# Commander.net
KiCad netlist of a schematic drawn in EAGLE
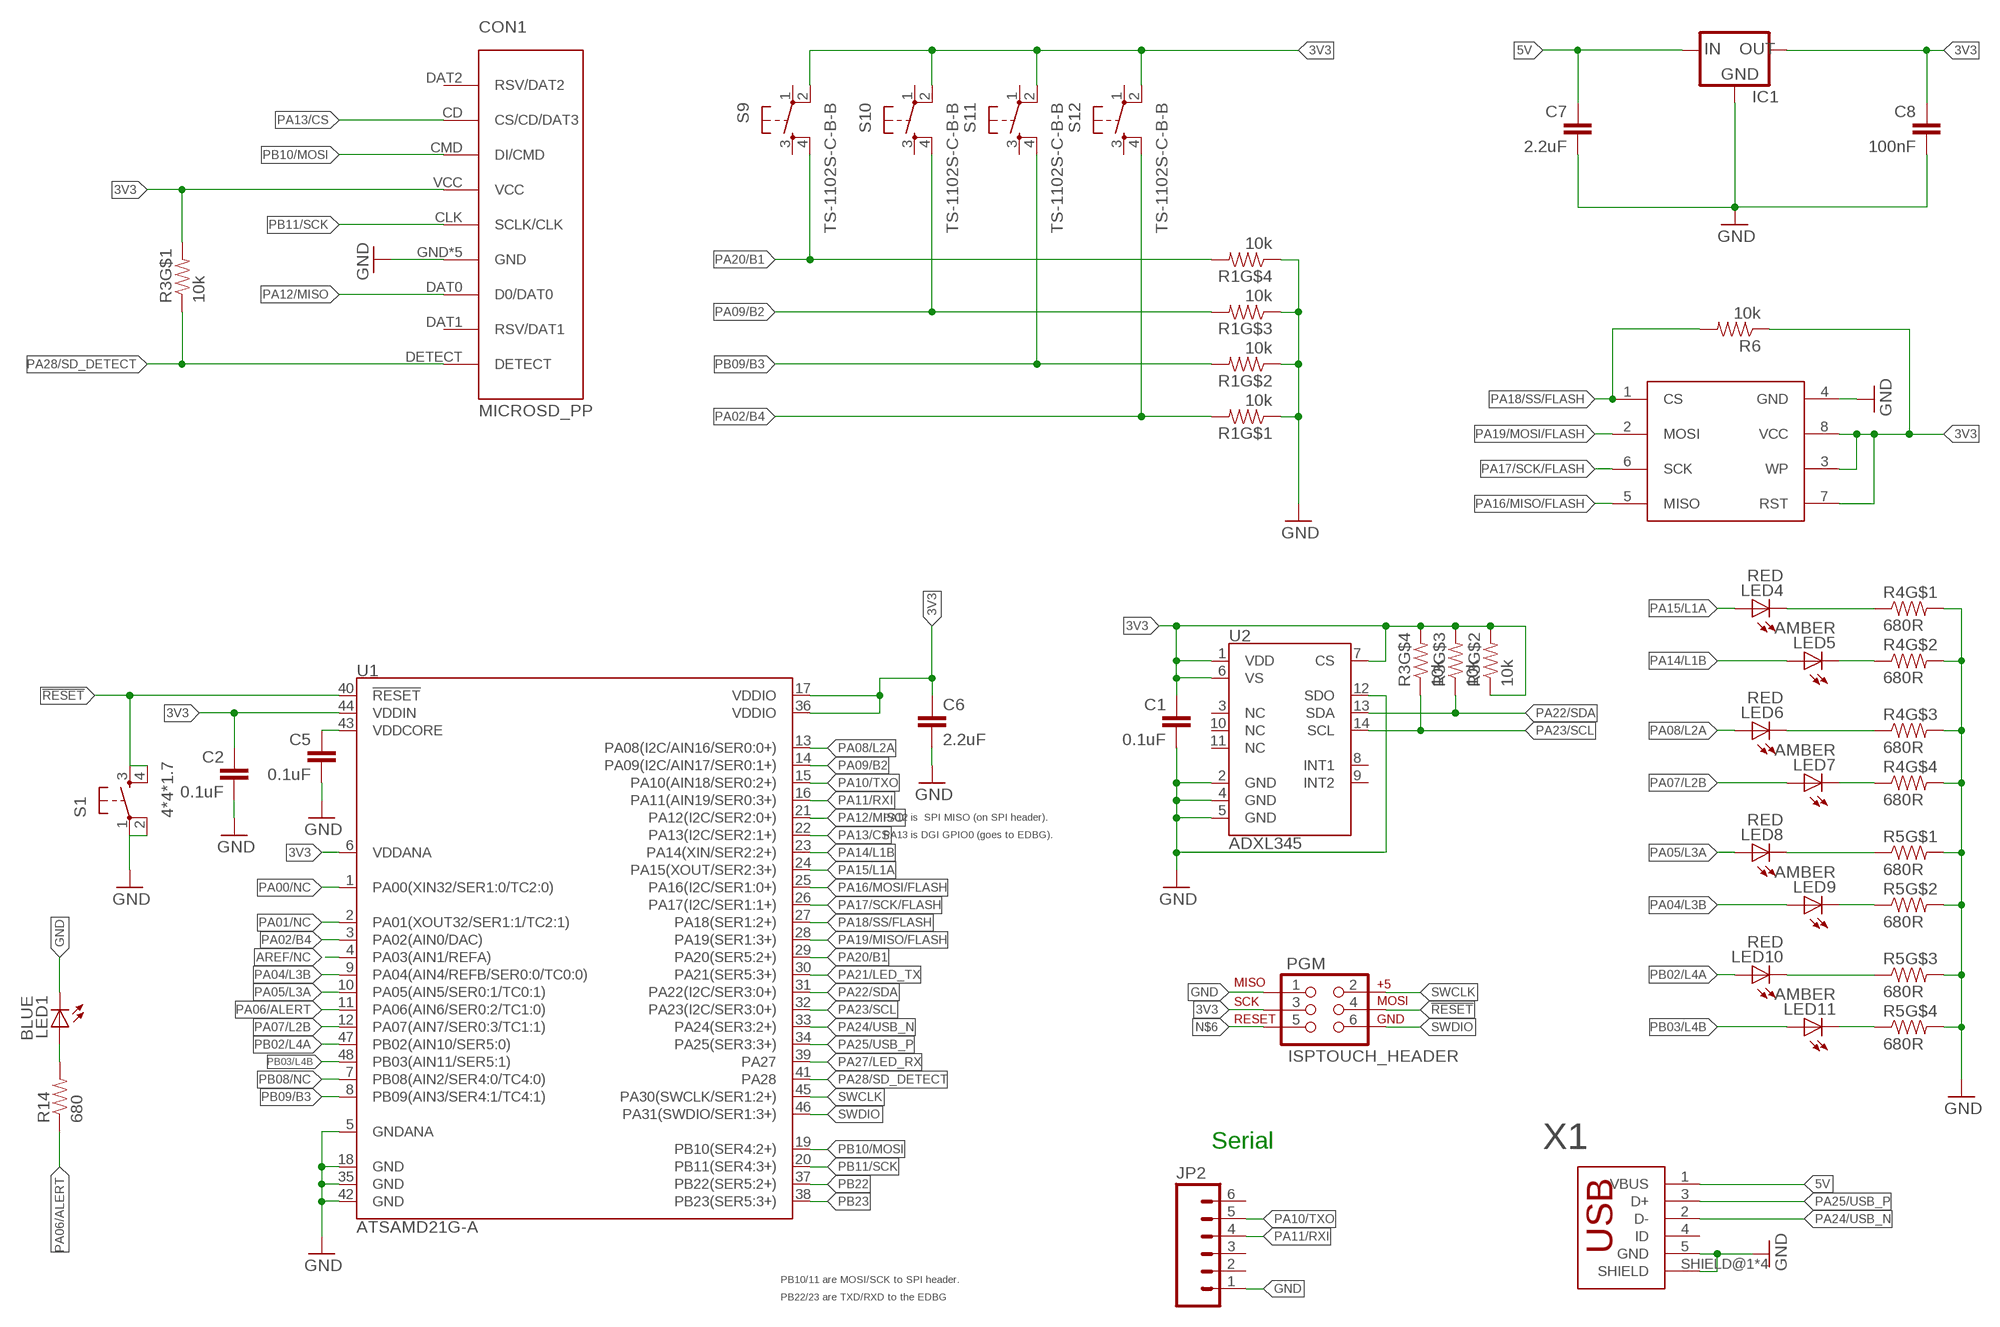
[diagram p0: schematic, sheet 1]

(export (version "E")
  (design (tool "Eeschema 10.0.6"))
  (components
    (comp (ref "C1")
      (value "0.1uF")
      (footprint "eagle-import:0805")
      (libsource (lib "eagle-import") (part "CAP0805"))
    )
    (comp (ref "C2")
      (value "0.1uF")
      (footprint "eagle-import:0805")
      (libsource (lib "eagle-import") (part "CAP0805"))
    )
    (comp (ref "C5")
      (value "0.1uF")
      (footprint "eagle-import:0805")
      (libsource (lib "eagle-import") (part "CAP0805"))
    )
    (comp (ref "C6")
      (value "2.2uF")
      (footprint "eagle-import:0805")
      (libsource (lib "eagle-import") (part "CAP0805"))
    )
    (comp (ref "C7")
      (value "2.2uF")
      (footprint "eagle-import:0805")
      (libsource (lib "eagle-import") (part "CAP0805"))
    )
    (comp (ref "C8")
      (value "100nF")
      (footprint "eagle-import:0805")
      (libsource (lib "eagle-import") (part "CAP0805"))
    )
    (comp (ref "CON1")
      (value "MICROSD_PP")
      (footprint "eagle-import:MICROSD_PP_NEW")
      (libsource (lib "eagle-import") (part "MICROSD_PP"))
    )
    (comp (ref "IC1")
      (value "VREG-LM1117SOT223")
      (footprint "eagle-import:SOT223")
      (libsource (lib "eagle-import") (part "VREG-LM1117SOT223"))
    )
    (comp (ref "JP2")
      (value "M06LOCK")
      (footprint "eagle-import:1X06_LOCK")
      (libsource (lib "eagle-import") (part "M06LOCK"))
    )
    (comp (ref "LED1")
      (value "BLUE")
      (footprint "eagle-import:CHIPLED_0805")
      (libsource (lib "eagle-import") (part "LEDCHIPLED_0805"))
    )
    (comp (ref "LED4")
      (value "RED")
      (footprint "eagle-import:CHIPLED_0805")
      (libsource (lib "eagle-import") (part "LEDCHIPLED_0805"))
    )
    (comp (ref "LED5")
      (value "AMBER")
      (footprint "eagle-import:CHIPLED_0805")
      (libsource (lib "eagle-import") (part "LEDCHIPLED_0805"))
    )
    (comp (ref "LED6")
      (value "RED")
      (footprint "eagle-import:CHIPLED_0805")
      (libsource (lib "eagle-import") (part "LEDCHIPLED_0805"))
    )
    (comp (ref "LED7")
      (value "AMBER")
      (footprint "eagle-import:CHIPLED_0805")
      (libsource (lib "eagle-import") (part "LEDCHIPLED_0805"))
    )
    (comp (ref "LED8")
      (value "RED")
      (footprint "eagle-import:CHIPLED_0805")
      (libsource (lib "eagle-import") (part "LEDCHIPLED_0805"))
    )
    (comp (ref "LED9")
      (value "AMBER")
      (footprint "eagle-import:CHIPLED_0805")
      (libsource (lib "eagle-import") (part "LEDCHIPLED_0805"))
    )
    (comp (ref "LED10")
      (value "RED")
      (footprint "eagle-import:CHIPLED_0805")
      (libsource (lib "eagle-import") (part "LEDCHIPLED_0805"))
    )
    (comp (ref "LED11")
      (value "AMBER")
      (footprint "eagle-import:CHIPLED_0805")
      (libsource (lib "eagle-import") (part "LEDCHIPLED_0805"))
    )
    (comp (ref "PGM")
      (value "ISPTOUCH_HEADER")
      (footprint "eagle-import:AVX_9188_6-WAY_MATING_GUIDE")
      (libsource (lib "eagle-import") (part "ISPTOUCH_HEADER"))
    )
    (comp (ref "R1")
      (value "10k")
      (footprint "eagle-import:YV_TC164")
      (libsource (lib "eagle-import") (part "YC/TC164"))
    )
    (comp (ref "R3")
      (value "10k")
      (footprint "eagle-import:YV_TC164")
      (libsource (lib "eagle-import") (part "YC/TC164"))
    )
    (comp (ref "R4")
      (value "680R")
      (footprint "eagle-import:YV_TC164")
      (libsource (lib "eagle-import") (part "YC/TC164"))
    )
    (comp (ref "R5")
      (value "680R")
      (footprint "eagle-import:YV_TC164")
      (libsource (lib "eagle-import") (part "YC/TC164"))
    )
    (comp (ref "R6")
      (value "10k")
      (footprint "eagle-import:0805")
      (libsource (lib "eagle-import") (part "RESISTOR0805-RES"))
    )
    (comp (ref "R14")
      (value "680")
      (footprint "eagle-import:0805")
      (libsource (lib "eagle-import") (part "RESISTOR0805-RES"))
    )
    (comp (ref "S1")
      (value "4*4*1.7")
      (footprint "eagle-import:BOOMELE-4X4X1.7")
      (libsource (lib "eagle-import") (part "TACTILE-SWITCH-4PIN441.7"))
    )
    (comp (ref "S9")
      (value "TS-1102S-C-B-B")
      (footprint "eagle-import:XKB_ENTERPRISE")
      (libsource (lib "eagle-import") (part "TACTILE-SWITCH-4PINTS-1102S-C-B-B"))
    )
    (comp (ref "S10")
      (value "TS-1102S-C-B-B")
      (footprint "eagle-import:XKB_ENTERPRISE")
      (libsource (lib "eagle-import") (part "TACTILE-SWITCH-4PINTS-1102S-C-B-B"))
    )
    (comp (ref "S11")
      (value "TS-1102S-C-B-B")
      (footprint "eagle-import:XKB_ENTERPRISE")
      (libsource (lib "eagle-import") (part "TACTILE-SWITCH-4PINTS-1102S-C-B-B"))
    )
    (comp (ref "S12")
      (value "TS-1102S-C-B-B")
      (footprint "eagle-import:XKB_ENTERPRISE")
      (libsource (lib "eagle-import") (part "TACTILE-SWITCH-4PINTS-1102S-C-B-B"))
    )
    (comp (ref "U$1")
      (value "W25Q128SOIC8")
      (footprint "eagle-import:SOIC8")
      (libsource (lib "eagle-import") (part "W25Q128SOIC8"))
    )
    (comp (ref "U1")
      (value "ATSAMD21G-A")
      (footprint "eagle-import:TQFP-48")
      (libsource (lib "eagle-import") (part "ATSAMD21G-A"))
    )
    (comp (ref "U2")
      (value "ADXL345")
      (footprint "eagle-import:LGA-14")
      (libsource (lib "eagle-import") (part "ADXL345"))
    )
    (comp (ref "X1")
      (value "ZX62D-B-5PA8SML")
      (footprint "eagle-import:ZX62D-B-5PA8_SMALL")
      (libsource (lib "eagle-import") (part "ZX62D-B-5PA8SML"))
    )
  )
  (nets
    (net (code "1") (name "/~{RESET}") (class "Default")
      (node (ref "PGM") (pin "4") (pinfunction "4_4") (pintype "passive"))
      (node (ref "S1") (pin "3") (pinfunction "3_3") (pintype "passive"))
      (node (ref "S1") (pin "4") (pinfunction "4_4") (pintype "passive"))
      (node (ref "U1") (pin "40") (pinfunction "~{RESET}_40") (pintype "bidirectional"))
    )
    (net (code "2") (name "3V3") (class "Default")
      (node (ref "C1") (pin "1") (pinfunction "1_1") (pintype "passive"))
      (node (ref "C2") (pin "1") (pinfunction "1_1") (pintype "passive"))
      (node (ref "C6") (pin "1") (pinfunction "1_1") (pintype "passive"))
      (node (ref "C8") (pin "1") (pinfunction "1_1") (pintype "passive"))
      (node (ref "CON1") (pin "VCC") (pinfunction "VCC_VCC") (pintype "bidirectional"))
      (node (ref "IC1") (pin "2") (pinfunction "OUT_2") (pintype "output"))
      (node (ref "IC1") (pin "4") (pinfunction "OUT_4") (pintype "output"))
      (node (ref "PGM") (pin "3") (pinfunction "3_3") (pintype "passive"))
      (node (ref "R3") (pin "2") (pinfunction "2_2") (pintype "passive"))
      (node (ref "R3") (pin "3") (pinfunction "1_3") (pintype "passive"))
      (node (ref "R3") (pin "4") (pinfunction "2_4") (pintype "passive"))
      (node (ref "R3") (pin "6") (pinfunction "2_6") (pintype "passive"))
      (node (ref "R3") (pin "8") (pinfunction "2_8") (pintype "passive"))
      (node (ref "R6") (pin "1") (pinfunction "1_1") (pintype "passive"))
      (node (ref "S10") (pin "2") (pinfunction "2_2") (pintype "passive"))
      (node (ref "S11") (pin "2") (pinfunction "2_2") (pintype "passive"))
      (node (ref "S12") (pin "2") (pinfunction "2_2") (pintype "passive"))
      (node (ref "S9") (pin "2") (pinfunction "2_2") (pintype "passive"))
      (node (ref "U$1") (pin "3") (pinfunction "WP_3") (pintype "bidirectional"))
      (node (ref "U$1") (pin "7") (pinfunction "RST_7") (pintype "bidirectional"))
      (node (ref "U$1") (pin "8") (pinfunction "VCC_8") (pintype "bidirectional"))
      (node (ref "U1") (pin "17") (pinfunction "VDDIO_17") (pintype "bidirectional"))
      (node (ref "U1") (pin "36") (pinfunction "VDDIO_36") (pintype "bidirectional"))
      (node (ref "U1") (pin "44") (pinfunction "VDDIN_44") (pintype "bidirectional"))
      (node (ref "U1") (pin "6") (pinfunction "VDDANA_6") (pintype "bidirectional"))
      (node (ref "U2") (pin "1") (pinfunction "VDD_1") (pintype "bidirectional"))
      (node (ref "U2") (pin "6") (pinfunction "VS_6") (pintype "bidirectional"))
      (node (ref "U2") (pin "7") (pinfunction "CS_7") (pintype "bidirectional"))
    )
    (net (code "3") (name "5V") (class "Default")
      (node (ref "C7") (pin "1") (pinfunction "1_1") (pintype "passive"))
      (node (ref "IC1") (pin "3") (pinfunction "IN_3") (pintype "input"))
      (node (ref "X1") (pin "1") (pinfunction "VBUS_1") (pintype "bidirectional"))
    )
    (net (code "4") (name "AREF{slash}NC") (class "Default")
      (node (ref "U1") (pin "4") (pinfunction "PA03(AIN1/REFA)_4") (pintype "bidirectional"))
    )
    (net (code "5") (name "GND") (class "Default")
      (node (ref "C1") (pin "2") (pinfunction "2_2") (pintype "passive"))
      (node (ref "C2") (pin "2") (pinfunction "2_2") (pintype "passive"))
      (node (ref "C5") (pin "2") (pinfunction "2_2") (pintype "passive"))
      (node (ref "C6") (pin "2") (pinfunction "2_2") (pintype "passive"))
      (node (ref "C7") (pin "2") (pinfunction "2_2") (pintype "passive"))
      (node (ref "C8") (pin "2") (pinfunction "2_2") (pintype "passive"))
      (node (ref "CON1") (pin "GND") (pinfunction "GND_GND") (pintype "bidirectional"))
      (node (ref "CON1") (pin "GND@1") (pinfunction "GND_GND@1") (pintype "bidirectional"))
      (node (ref "CON1") (pin "GND@2") (pinfunction "GND_GND@2") (pintype "bidirectional"))
      (node (ref "CON1") (pin "GND@3") (pinfunction "GND_GND@3") (pintype "bidirectional"))
      (node (ref "CON1") (pin "GND@4") (pinfunction "GND_GND@4") (pintype "bidirectional"))
      (node (ref "IC1") (pin "1") (pinfunction "GND_1") (pintype "input"))
      (node (ref "JP2") (pin "1") (pinfunction "1_1") (pintype "passive"))
      (node (ref "LED1") (pin "C") (pinfunction "C_C") (pintype "passive"))
      (node (ref "PGM") (pin "1") (pinfunction "1_1") (pintype "passive"))
      (node (ref "R1") (pin "1") (pinfunction "1_1") (pintype "passive"))
      (node (ref "R1") (pin "3") (pinfunction "1_3") (pintype "passive"))
      (node (ref "R1") (pin "5") (pinfunction "1_5") (pintype "passive"))
      (node (ref "R1") (pin "7") (pinfunction "1_7") (pintype "passive"))
      (node (ref "R4") (pin "2") (pinfunction "2_2") (pintype "passive"))
      (node (ref "R4") (pin "4") (pinfunction "2_4") (pintype "passive"))
      (node (ref "R4") (pin "6") (pinfunction "2_6") (pintype "passive"))
      (node (ref "R4") (pin "8") (pinfunction "2_8") (pintype "passive"))
      (node (ref "R5") (pin "2") (pinfunction "2_2") (pintype "passive"))
      (node (ref "R5") (pin "4") (pinfunction "2_4") (pintype "passive"))
      (node (ref "R5") (pin "6") (pinfunction "2_6") (pintype "passive"))
      (node (ref "R5") (pin "8") (pinfunction "2_8") (pintype "passive"))
      (node (ref "S1") (pin "1") (pinfunction "1_1") (pintype "passive"))
      (node (ref "S1") (pin "2") (pinfunction "2_2") (pintype "passive"))
      (node (ref "U$1") (pin "4") (pinfunction "GND_4") (pintype "bidirectional"))
      (node (ref "U1") (pin "18") (pinfunction "GND_18") (pintype "bidirectional"))
      (node (ref "U1") (pin "35") (pinfunction "GND_35") (pintype "bidirectional"))
      (node (ref "U1") (pin "42") (pinfunction "GND_42") (pintype "bidirectional"))
      (node (ref "U1") (pin "5") (pinfunction "GNDANA_5") (pintype "bidirectional"))
      (node (ref "U2") (pin "12") (pinfunction "SDO_12") (pintype "bidirectional"))
      (node (ref "U2") (pin "2") (pinfunction "GND_2") (pintype "bidirectional"))
      (node (ref "U2") (pin "4") (pinfunction "GND_4") (pintype "bidirectional"))
      (node (ref "U2") (pin "5") (pinfunction "GND_5") (pintype "bidirectional"))
      (node (ref "X1") (pin "5") (pinfunction "GND_5") (pintype "bidirectional"))
      (node (ref "X1") (pin "SHIELD@1") (pinfunction "SHIELD_SHIELD@1") (pintype "bidirectional"))
      (node (ref "X1") (pin "SHIELD@2") (pinfunction "SHIELD_SHIELD@2") (pintype "bidirectional"))
      (node (ref "X1") (pin "SHIELD@3") (pinfunction "SHIELD_SHIELD@3") (pintype "bidirectional"))
      (node (ref "X1") (pin "SHIELD@4") (pinfunction "SHIELD_SHIELD@4") (pintype "bidirectional"))
    )
    (net (code "6") (name "N$6") (class "Default")
      (node (ref "PGM") (pin "5") (pinfunction "5_5") (pintype "passive"))
    )
    (net (code "7") (name "Net-(LED1-PadA)") (class "Default")
      (node (ref "LED1") (pin "A") (pinfunction "A_A") (pintype "passive"))
      (node (ref "R14") (pin "2") (pinfunction "2_2") (pintype "passive"))
    )
    (net (code "8") (name "Net-(LED4-PadC)") (class "Default")
      (node (ref "LED4") (pin "C") (pinfunction "C_C") (pintype "passive"))
      (node (ref "R4") (pin "1") (pinfunction "1_1") (pintype "passive"))
    )
    (net (code "9") (name "Net-(LED8-PadC)") (class "Default")
      (node (ref "LED8") (pin "C") (pinfunction "C_C") (pintype "passive"))
      (node (ref "R5") (pin "1") (pinfunction "1_1") (pintype "passive"))
    )
    (net (code "10") (name "Net-(R4B-1)") (class "Default")
      (node (ref "LED5") (pin "C") (pinfunction "C_C") (pintype "passive"))
      (node (ref "R4") (pin "3") (pinfunction "1_3") (pintype "passive"))
    )
    (net (code "11") (name "Net-(R4C-1)") (class "Default")
      (node (ref "LED6") (pin "C") (pinfunction "C_C") (pintype "passive"))
      (node (ref "R4") (pin "5") (pinfunction "1_5") (pintype "passive"))
    )
    (net (code "12") (name "Net-(R4D-1)") (class "Default")
      (node (ref "LED7") (pin "C") (pinfunction "C_C") (pintype "passive"))
      (node (ref "R4") (pin "7") (pinfunction "1_7") (pintype "passive"))
    )
    (net (code "13") (name "Net-(R5B-1)") (class "Default")
      (node (ref "LED9") (pin "C") (pinfunction "C_C") (pintype "passive"))
      (node (ref "R5") (pin "3") (pinfunction "1_3") (pintype "passive"))
    )
    (net (code "14") (name "Net-(R5C-1)") (class "Default")
      (node (ref "LED10") (pin "C") (pinfunction "C_C") (pintype "passive"))
      (node (ref "R5") (pin "5") (pinfunction "1_5") (pintype "passive"))
    )
    (net (code "15") (name "Net-(R5D-1)") (class "Default")
      (node (ref "LED11") (pin "C") (pinfunction "C_C") (pintype "passive"))
      (node (ref "R5") (pin "7") (pinfunction "1_7") (pintype "passive"))
    )
    (net (code "16") (name "Net-(U1-VDDCORE)") (class "Default")
      (node (ref "C5") (pin "1") (pinfunction "1_1") (pintype "passive"))
      (node (ref "U1") (pin "43") (pinfunction "VDDCORE_43") (pintype "bidirectional"))
    )
    (net (code "17") (name "PA00{slash}NC") (class "Default")
      (node (ref "U1") (pin "1") (pinfunction "PA00(XIN32/SER1:0/TC2:0)_1") (pintype "bidirectional"))
    )
    (net (code "18") (name "PA01{slash}NC") (class "Default")
      (node (ref "U1") (pin "2") (pinfunction "PA01(XOUT32/SER1:1/TC2:1)_2") (pintype "bidirectional"))
    )
    (net (code "19") (name "PA02{slash}B4") (class "Default")
      (node (ref "R1") (pin "2") (pinfunction "2_2") (pintype "passive"))
      (node (ref "S12") (pin "4") (pinfunction "4_4") (pintype "passive"))
      (node (ref "U1") (pin "3") (pinfunction "PA02(AIN0/DAC)_3") (pintype "bidirectional"))
    )
    (net (code "20") (name "PA04{slash}L3B") (class "Default")
      (node (ref "LED9") (pin "A") (pinfunction "A_A") (pintype "passive"))
      (node (ref "U1") (pin "9") (pinfunction "PA04(AIN4/REFB/SER0:0/TC0:0)_9") (pintype "bidirectional"))
    )
    (net (code "21") (name "PA05{slash}L3A") (class "Default")
      (node (ref "LED8") (pin "A") (pinfunction "A_A") (pintype "passive"))
      (node (ref "U1") (pin "10") (pinfunction "PA05(AIN5/SER0:1/TC0:1)_10") (pintype "bidirectional"))
    )
    (net (code "22") (name "PA06{slash}ALERT") (class "Default")
      (node (ref "R14") (pin "1") (pinfunction "1_1") (pintype "passive"))
      (node (ref "U1") (pin "11") (pinfunction "PA06(AIN6/SER0:2/TC1:0)_11") (pintype "bidirectional"))
    )
    (net (code "23") (name "PA07{slash}L2B") (class "Default")
      (node (ref "LED7") (pin "A") (pinfunction "A_A") (pintype "passive"))
      (node (ref "U1") (pin "12") (pinfunction "PA07(AIN7/SER0:3/TC1:1)_12") (pintype "bidirectional"))
    )
    (net (code "24") (name "PA08{slash}L2A") (class "Default")
      (node (ref "LED6") (pin "A") (pinfunction "A_A") (pintype "passive"))
      (node (ref "U1") (pin "13") (pinfunction "PA08(I2C/AIN16/SER0:0+)_13") (pintype "bidirectional"))
    )
    (net (code "25") (name "PA09{slash}B2") (class "Default")
      (node (ref "R1") (pin "6") (pinfunction "2_6") (pintype "passive"))
      (node (ref "S10") (pin "4") (pinfunction "4_4") (pintype "passive"))
      (node (ref "U1") (pin "14") (pinfunction "PA09(I2C/AIN17/SER0:1+)_14") (pintype "bidirectional"))
    )
    (net (code "26") (name "PA10{slash}TXO") (class "Default")
      (node (ref "JP2") (pin "5") (pinfunction "5_5") (pintype "passive"))
      (node (ref "U1") (pin "15") (pinfunction "PA10(AIN18/SER0:2+)_15") (pintype "bidirectional"))
    )
    (net (code "27") (name "PA11{slash}RXI") (class "Default")
      (node (ref "JP2") (pin "4") (pinfunction "4_4") (pintype "passive"))
      (node (ref "U1") (pin "16") (pinfunction "PA11(AIN19/SER0:3+)_16") (pintype "bidirectional"))
    )
    (net (code "28") (name "PA12{slash}MISO") (class "Default")
      (node (ref "CON1") (pin "DAT0") (pinfunction "D0/DAT0_DAT0") (pintype "bidirectional"))
      (node (ref "U1") (pin "21") (pinfunction "PA12(I2C/SER2:0+)_21") (pintype "bidirectional"))
    )
    (net (code "29") (name "PA13{slash}CS") (class "Default")
      (node (ref "CON1") (pin "CD") (pinfunction "CS/CD/DAT3_CD") (pintype "bidirectional"))
      (node (ref "U1") (pin "22") (pinfunction "PA13(I2C/SER2:1+)_22") (pintype "bidirectional"))
    )
    (net (code "30") (name "PA14{slash}L1B") (class "Default")
      (node (ref "LED5") (pin "A") (pinfunction "A_A") (pintype "passive"))
      (node (ref "U1") (pin "23") (pinfunction "PA14(XIN/SER2:2+)_23") (pintype "bidirectional"))
    )
    (net (code "31") (name "PA15{slash}L1A") (class "Default")
      (node (ref "LED4") (pin "A") (pinfunction "A_A") (pintype "passive"))
      (node (ref "U1") (pin "24") (pinfunction "PA15(XOUT/SER2:3+)_24") (pintype "bidirectional"))
    )
    (net (code "32") (name "PA16{slash}MISO{slash}FLASH") (class "Default")
      (node (ref "U$1") (pin "5") (pinfunction "MISO_5") (pintype "bidirectional"))
    )
    (net (code "33") (name "PA16{slash}MOSI{slash}FLASH") (class "Default")
      (node (ref "U1") (pin "25") (pinfunction "PA16(I2C/SER1:0+)_25") (pintype "bidirectional"))
    )
    (net (code "34") (name "PA17{slash}SCK{slash}FLASH") (class "Default")
      (node (ref "U$1") (pin "6") (pinfunction "SCK_6") (pintype "bidirectional"))
      (node (ref "U1") (pin "26") (pinfunction "PA17(I2C/SER1:1+)_26") (pintype "bidirectional"))
    )
    (net (code "35") (name "PA18{slash}SS{slash}FLASH") (class "Default")
      (node (ref "R6") (pin "2") (pinfunction "2_2") (pintype "passive"))
      (node (ref "U$1") (pin "1") (pinfunction "CS_1") (pintype "bidirectional"))
      (node (ref "U1") (pin "27") (pinfunction "PA18(SER1:2+)_27") (pintype "bidirectional"))
    )
    (net (code "36") (name "PA19{slash}MISO{slash}FLASH") (class "Default")
      (node (ref "U1") (pin "28") (pinfunction "PA19(SER1:3+)_28") (pintype "bidirectional"))
    )
    (net (code "37") (name "PA19{slash}MOSI{slash}FLASH") (class "Default")
      (node (ref "U$1") (pin "2") (pinfunction "MOSI_2") (pintype "bidirectional"))
    )
    (net (code "38") (name "PA20{slash}B1") (class "Default")
      (node (ref "R1") (pin "8") (pinfunction "2_8") (pintype "passive"))
      (node (ref "S9") (pin "4") (pinfunction "4_4") (pintype "passive"))
      (node (ref "U1") (pin "29") (pinfunction "PA20(SER5:2+)_29") (pintype "bidirectional"))
    )
    (net (code "39") (name "PA21{slash}LED_TX") (class "Default")
      (node (ref "U1") (pin "30") (pinfunction "PA21(SER5:3+)_30") (pintype "bidirectional"))
    )
    (net (code "40") (name "PA22{slash}SDA") (class "Default")
      (node (ref "R3") (pin "5") (pinfunction "1_5") (pintype "passive"))
      (node (ref "U1") (pin "31") (pinfunction "PA22(I2C/SER3:0+)_31") (pintype "bidirectional"))
      (node (ref "U2") (pin "13") (pinfunction "SDA_13") (pintype "bidirectional"))
    )
    (net (code "41") (name "PA23{slash}SCL") (class "Default")
      (node (ref "R3") (pin "7") (pinfunction "1_7") (pintype "passive"))
      (node (ref "U1") (pin "32") (pinfunction "PA23(I2C/SER3:0+)_32") (pintype "bidirectional"))
      (node (ref "U2") (pin "14") (pinfunction "SCL_14") (pintype "bidirectional"))
    )
    (net (code "42") (name "PA24{slash}USB_N") (class "Default")
      (node (ref "U1") (pin "33") (pinfunction "PA24(SER3:2+)_33") (pintype "bidirectional"))
      (node (ref "X1") (pin "2") (pinfunction "D-_2") (pintype "bidirectional"))
    )
    (net (code "43") (name "PA25{slash}USB_P") (class "Default")
      (node (ref "U1") (pin "34") (pinfunction "PA25(SER3:3+)_34") (pintype "bidirectional"))
      (node (ref "X1") (pin "3") (pinfunction "D+_3") (pintype "bidirectional"))
    )
    (net (code "44") (name "PA27{slash}LED_RX") (class "Default")
      (node (ref "U1") (pin "39") (pinfunction "PA27_39") (pintype "bidirectional"))
    )
    (net (code "45") (name "PA28{slash}SD_DETECT") (class "Default")
      (node (ref "CON1") (pin "DETECT") (pinfunction "DETECT_DETECT") (pintype "bidirectional"))
      (node (ref "R3") (pin "1") (pinfunction "1_1") (pintype "passive"))
      (node (ref "U1") (pin "41") (pinfunction "PA28_41") (pintype "bidirectional"))
    )
    (net (code "46") (name "PB02{slash}L4A") (class "Default")
      (node (ref "LED10") (pin "A") (pinfunction "A_A") (pintype "passive"))
      (node (ref "U1") (pin "47") (pinfunction "PB02(AIN10/SER5:0)_47") (pintype "bidirectional"))
    )
    (net (code "47") (name "PB03{slash}L4B") (class "Default")
      (node (ref "LED11") (pin "A") (pinfunction "A_A") (pintype "passive"))
      (node (ref "U1") (pin "48") (pinfunction "PB03(AIN11/SER5:1)_48") (pintype "bidirectional"))
    )
    (net (code "48") (name "PB08{slash}NC") (class "Default")
      (node (ref "U1") (pin "7") (pinfunction "PB08(AIN2/SER4:0/TC4:0)_7") (pintype "bidirectional"))
    )
    (net (code "49") (name "PB09{slash}B3") (class "Default")
      (node (ref "R1") (pin "4") (pinfunction "2_4") (pintype "passive"))
      (node (ref "S11") (pin "4") (pinfunction "4_4") (pintype "passive"))
      (node (ref "U1") (pin "8") (pinfunction "PB09(AIN3/SER4:1/TC4:1)_8") (pintype "bidirectional"))
    )
    (net (code "50") (name "PB10{slash}MOSI") (class "Default")
      (node (ref "CON1") (pin "CMD") (pinfunction "DI/CMD_CMD") (pintype "bidirectional"))
      (node (ref "U1") (pin "19") (pinfunction "PB10(SER4:2+)_19") (pintype "bidirectional"))
    )
    (net (code "51") (name "PB11{slash}SCK") (class "Default")
      (node (ref "CON1") (pin "CLK") (pinfunction "SCLK/CLK_CLK") (pintype "bidirectional"))
      (node (ref "U1") (pin "20") (pinfunction "PB11(SER4:3+)_20") (pintype "bidirectional"))
    )
    (net (code "52") (name "PB22") (class "Default")
      (node (ref "U1") (pin "37") (pinfunction "PB22(SER5:2+)_37") (pintype "bidirectional"))
    )
    (net (code "53") (name "PB23") (class "Default")
      (node (ref "U1") (pin "38") (pinfunction "PB23(SER5:3+)_38") (pintype "bidirectional"))
    )
    (net (code "54") (name "SWCLK") (class "Default")
      (node (ref "PGM") (pin "2") (pinfunction "2_2") (pintype "passive"))
      (node (ref "U1") (pin "45") (pinfunction "PA30(SWCLK/SER1:2+)_45") (pintype "bidirectional"))
    )
    (net (code "55") (name "SWDIO") (class "Default")
      (node (ref "PGM") (pin "6") (pinfunction "6_6") (pintype "passive"))
      (node (ref "U1") (pin "46") (pinfunction "PA31(SWDIO/SER1:3+)_46") (pintype "bidirectional"))
    )
    (net (code "56") (name "unconnected-(CON1-RSV{slash}DAT1-PadDAT1)") (class "Default")
      (node (ref "CON1") (pin "DAT1") (pinfunction "RSV/DAT1_DAT1") (pintype "bidirectional"))
    )
    (net (code "57") (name "unconnected-(CON1-RSV{slash}DAT2-PadDAT2)") (class "Default")
      (node (ref "CON1") (pin "DAT2") (pinfunction "RSV/DAT2_DAT2") (pintype "bidirectional"))
    )
    (net (code "58") (name "unconnected-(JP2-Pad2)") (class "Default")
      (node (ref "JP2") (pin "2") (pinfunction "2_2") (pintype "passive"))
    )
    (net (code "59") (name "unconnected-(JP2-Pad3)") (class "Default")
      (node (ref "JP2") (pin "3") (pinfunction "3_3") (pintype "passive"))
    )
    (net (code "60") (name "unconnected-(JP2-Pad6)") (class "Default")
      (node (ref "JP2") (pin "6") (pinfunction "6_6") (pintype "passive"))
    )
    (net (code "61") (name "unconnected-(S9-Pad1)") (class "Default")
      (node (ref "S9") (pin "1") (pinfunction "1_1") (pintype "passive"))
    )
    (net (code "62") (name "unconnected-(S9-Pad3)") (class "Default")
      (node (ref "S9") (pin "3") (pinfunction "3_3") (pintype "passive"))
    )
    (net (code "63") (name "unconnected-(S10-Pad1)") (class "Default")
      (node (ref "S10") (pin "1") (pinfunction "1_1") (pintype "passive"))
    )
    (net (code "64") (name "unconnected-(S10-Pad3)") (class "Default")
      (node (ref "S10") (pin "3") (pinfunction "3_3") (pintype "passive"))
    )
    (net (code "65") (name "unconnected-(S11-Pad1)") (class "Default")
      (node (ref "S11") (pin "1") (pinfunction "1_1") (pintype "passive"))
    )
    (net (code "66") (name "unconnected-(S11-Pad3)") (class "Default")
      (node (ref "S11") (pin "3") (pinfunction "3_3") (pintype "passive"))
    )
    (net (code "67") (name "unconnected-(S12-Pad1)") (class "Default")
      (node (ref "S12") (pin "1") (pinfunction "1_1") (pintype "passive"))
    )
    (net (code "68") (name "unconnected-(S12-Pad3)") (class "Default")
      (node (ref "S12") (pin "3") (pinfunction "3_3") (pintype "passive"))
    )
    (net (code "69") (name "unconnected-(U2-INT1-Pad8)") (class "Default")
      (node (ref "U2") (pin "8") (pinfunction "INT1_8") (pintype "bidirectional"))
    )
    (net (code "70") (name "unconnected-(U2-INT2-Pad9)") (class "Default")
      (node (ref "U2") (pin "9") (pinfunction "INT2_9") (pintype "bidirectional"))
    )
    (net (code "71") (name "unconnected-(U2-NC-Pad3)") (class "Default")
      (node (ref "U2") (pin "3") (pinfunction "NC_3") (pintype "bidirectional"))
    )
    (net (code "72") (name "unconnected-(U2-NC-Pad10)") (class "Default")
      (node (ref "U2") (pin "10") (pinfunction "NC_10") (pintype "bidirectional"))
    )
    (net (code "73") (name "unconnected-(U2-NC-Pad11)") (class "Default")
      (node (ref "U2") (pin "11") (pinfunction "NC_11") (pintype "bidirectional"))
    )
    (net (code "74") (name "unconnected-(X1-ID-Pad4)") (class "Default")
      (node (ref "X1") (pin "4") (pinfunction "ID_4") (pintype "bidirectional"))
    )
  )
)
